# 3V3_LDO.net
KiCad netlist of a schematic drawn in Altium Designer
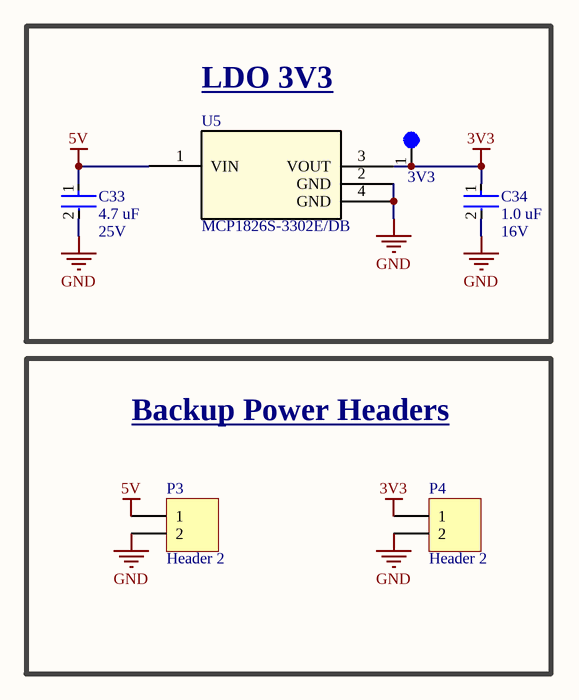
[diagram p0: 3V3_LDO.SchDoc]

(export (version "E")
  (design (tool "Eeschema 10.0.6"))
  (components
    (comp (ref "3V3")
      (value "5003")
      (footprint "TEST-POINT-0001")
      (description "Oranange PC Test Point, Miniature Phoisphor Bronze Silver Plating Through Hole Mounting Type")
      (libsource (lib "JLC_25") (part "TEST-POINT-0001"))
    )
    (comp (ref "C33")
      (value "CC0603KRX5R8BB475")
      (footprint "CAP-0603")
      (description "CAP CER 4.7UF 25V X5R 0603")
      (fields (field (name "CAPACITANCE") "4.7 uF") (field (name "VOLTAGE") "25V"))
      (libsource (lib "JLC_25") (part "CAP-4.7U-0001"))
    )
    (comp (ref "C34")
      (value "CC0603KRX7R7BB105")
      (footprint "CAP-0603")
      (description "CAP CER 1UF 16V X7R 0603")
      (fields (field (name "CAPACITANCE") "1.0 uF") (field (name "VOLTAGE") "16V"))
      (libsource (lib "JLC_25") (part "CAP-1U-0002"))
    )
    (comp (ref "P3")
      (value "Header 2")
      (footprint "HDR1X2")
      (description "Header, 2-Pin")
      (fields (field (name "PUBLISHER") "Altium Limited"))
      (libsource (lib "Miscellaneous Connectors") (part "Header 2"))
    )
    (comp (ref "P4")
      (value "Header 2")
      (footprint "HDR1X2")
      (description "Header, 2-Pin")
      (fields (field (name "PUBLISHER") "Altium Limited"))
      (libsource (lib "Miscellaneous Connectors") (part "Header 2"))
    )
    (comp (ref "U5")
      (value "MCP1826S-3302E/DB")
      (footprint "SOT-223_3MC_MCH")
      (description "Linear Voltage Regulator IC Positive Fixed 1 Output 1A SOT-223-3")
      (fields (field (name "COPYRIGHT") "Copyright (C) 2025 Ultra Librarian. All rights reserved."))
      (libsource (lib "JLC_25") (part "IC-LDO-0003"))
    )
  )
  (nets
    (net (code "1") (name "3V3") (class "Default")
      (node (ref "3V3") (pin "1") (pinfunction "0_1") (pintype "passive"))
      (node (ref "C34") (pin "1") (pinfunction "1_1") (pintype "passive"))
      (node (ref "P4") (pin "1") (pinfunction "1_1") (pintype "passive"))
      (node (ref "U5") (pin "3") (pinfunction "VOUT_3") (pintype "passive"))
    )
    (net (code "2") (name "5V") (class "Default")
      (node (ref "C33") (pin "1") (pinfunction "1_1") (pintype "passive"))
      (node (ref "P3") (pin "1") (pinfunction "1_1") (pintype "passive"))
      (node (ref "U5") (pin "1") (pinfunction "VIN_1") (pintype "passive"))
    )
    (net (code "3") (name "GND") (class "Default")
      (node (ref "C33") (pin "2") (pinfunction "2_2") (pintype "passive"))
      (node (ref "C34") (pin "2") (pinfunction "2_2") (pintype "passive"))
      (node (ref "P3") (pin "2") (pinfunction "2_2") (pintype "passive"))
      (node (ref "P4") (pin "2") (pinfunction "2_2") (pintype "passive"))
      (node (ref "U5") (pin "2") (pinfunction "GND_2") (pintype "passive"))
      (node (ref "U5") (pin "4") (pinfunction "GND_4") (pintype "passive"))
    )
  )
)
